# bicyclelab-manager-keyde-v4_0.net
KiCad netlist of a schematic drawn in EAGLE
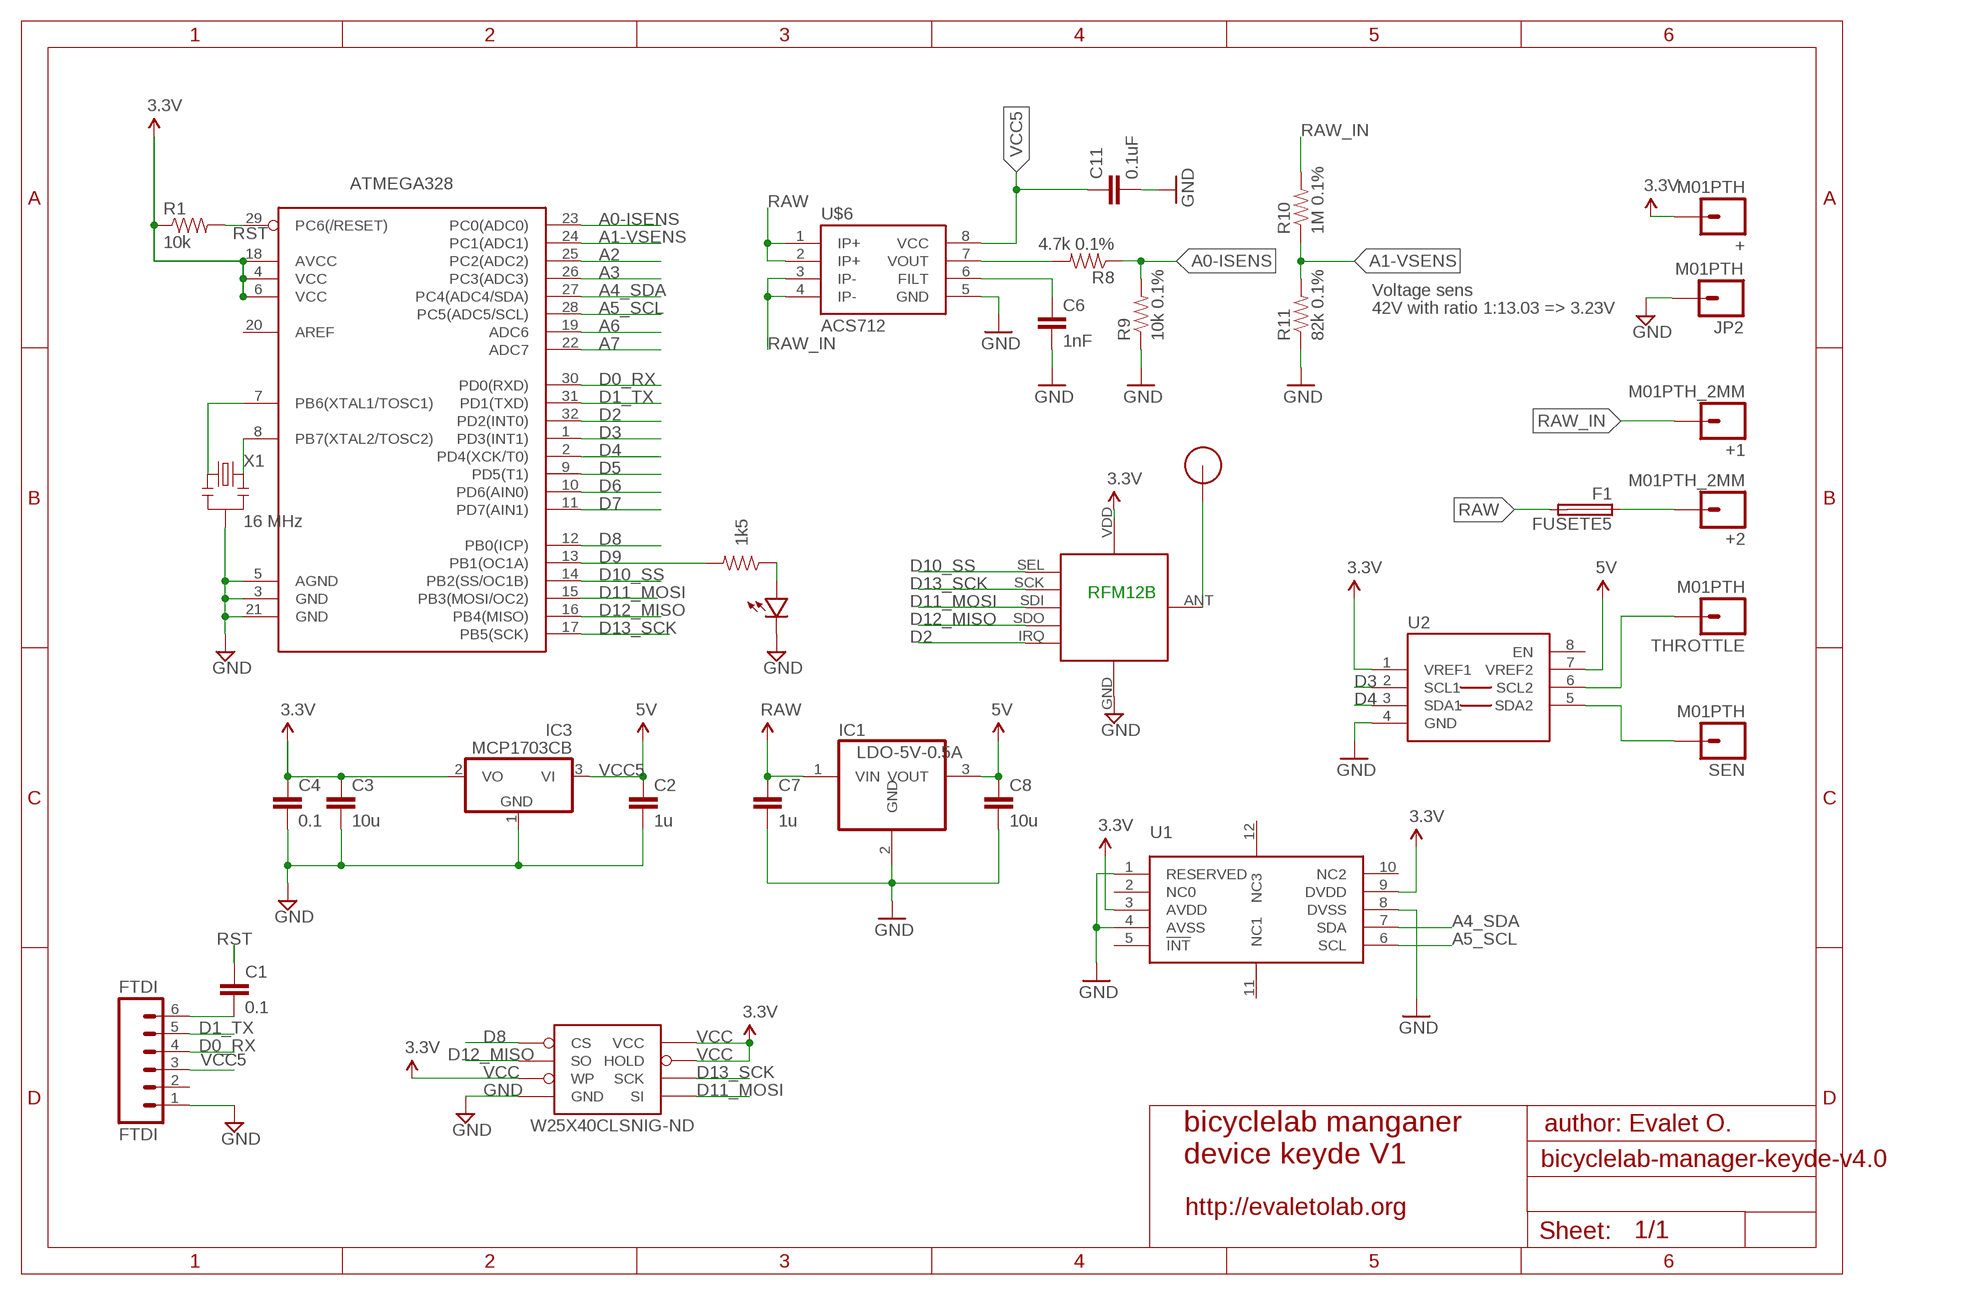
[diagram p0: schematic, sheet 1]

(export (version "E")
  (design (tool "Eeschema 10.0.6"))
  (components
    (comp (ref "+")
      (value "M01PTH")
      (footprint "eagle-import:1X01")
      (libsource (lib "eagle-import") (part "M01PTH"))
    )
    (comp (ref "+1")
      (value "M01PTH_2MM")
      (footprint "eagle-import:1X01_2MM")
      (libsource (lib "eagle-import") (part "M01PTH_2MM"))
    )
    (comp (ref "+2")
      (value "M01PTH_2MM")
      (footprint "eagle-import:1X01_2MM")
      (libsource (lib "eagle-import") (part "M01PTH_2MM"))
    )
    (comp (ref "ATMEGA328")
      (value "ATMega-328")
      (footprint "eagle-import:TQFP32-08")
      (libsource (lib "eagle-import") (part "ATMEGA168/328TQFP32"))
    )
    (comp (ref "C1")
      (value "0.1")
      (footprint "eagle-import:0603-CAP")
      (libsource (lib "eagle-import") (part "CAP0603-CAP"))
    )
    (comp (ref "C2")
      (value "1u")
      (footprint "eagle-import:0603-CAP")
      (libsource (lib "eagle-import") (part "CAP0603-CAP"))
    )
    (comp (ref "C3")
      (value "10u")
      (footprint "eagle-import:0805-CAP")
      (libsource (lib "eagle-import") (part "CAP0805-CAP"))
    )
    (comp (ref "C4")
      (value "0.1")
      (footprint "eagle-import:0603-CAP")
      (libsource (lib "eagle-import") (part "CAP0603-CAP"))
    )
    (comp (ref "C6")
      (value "1nF")
      (footprint "eagle-import:0805")
      (libsource (lib "eagle-import") (part "SparkFun_CAP0805"))
    )
    (comp (ref "C7")
      (value "1u")
      (footprint "eagle-import:0603-CAP")
      (libsource (lib "eagle-import") (part "CAP0603-CAP"))
    )
    (comp (ref "C8")
      (value "10u")
      (footprint "eagle-import:0805-CAP")
      (libsource (lib "eagle-import") (part "CAP0805-CAP"))
    )
    (comp (ref "C11")
      (value "0.1uF")
      (footprint "eagle-import:0805")
      (libsource (lib "eagle-import") (part "SparkFun_CAP0805"))
    )
    (comp (ref "F1")
      (value "FUSETE5")
      (footprint "eagle-import:TE5")
      (libsource (lib "eagle-import") (part "FUSETE5"))
    )
    (comp (ref "FTDI")
      (value "FTDI")
      (footprint "eagle-import:1X06")
      (libsource (lib "eagle-import") (part "M06SIP"))
    )
    (comp (ref "IC1")
      (value "LDO-5V-0.5A")
      (footprint "eagle-import:SOT223")
      (libsource (lib "eagle-import") (part "LDO-5V-0.5A"))
    )
    (comp (ref "IC3")
      (value "MCP1703CB")
      (footprint "eagle-import:SOT23")
      (libsource (lib "eagle-import") (part "MCP1703CB"))
    )
    (comp (ref "JP2")
      (value "M01PTH")
      (footprint "eagle-import:1X01")
      (libsource (lib "eagle-import") (part "M01PTH"))
    )
    (comp (ref "R1")
      (value "10k")
      (footprint "eagle-import:0603-RES")
      (libsource (lib "eagle-import") (part "RESISTOR0603-RES"))
    )
    (comp (ref "R2")
      (value "1k5")
      (footprint "eagle-import:0603-RES")
      (libsource (lib "eagle-import") (part "RESISTOR0603-RES"))
    )
    (comp (ref "R8")
      (value "4.7k 0.1%")
      (footprint "eagle-import:0805")
      (libsource (lib "eagle-import") (part "RESISTOR"))
    )
    (comp (ref "R9")
      (value "10k 0.1%")
      (footprint "eagle-import:0805")
      (libsource (lib "eagle-import") (part "RESISTOR"))
    )
    (comp (ref "R10")
      (value "1M 0.1%")
      (footprint "eagle-import:0805")
      (libsource (lib "eagle-import") (part "RESISTOR"))
    )
    (comp (ref "R11")
      (value "82k 0.1%")
      (footprint "eagle-import:0805")
      (libsource (lib "eagle-import") (part "RESISTOR"))
    )
    (comp (ref "RFM12B")
      (value "RFM12B_MINPADS")
      (footprint "eagle-import:RFM12B-MINPADS")
      (libsource (lib "eagle-import") (part "RFM12B_MINPADS"))
    )
    (comp (ref "SEN")
      (value "M01PTH")
      (footprint "eagle-import:1X01")
      (libsource (lib "eagle-import") (part "M01PTH"))
    )
    (comp (ref "THROTTLE")
      (value "M01PTH")
      (footprint "eagle-import:1X01")
      (libsource (lib "eagle-import") (part "M01PTH"))
    )
    (comp (ref "U$1")
      (value "RFM12B_ANTENNA")
      (footprint "eagle-import:RFM12B-ANTENNA")
      (libsource (lib "eagle-import") (part "RFM12B_ANTENNA"))
    )
    (comp (ref "U$2")
      (value "LED0603")
      (footprint "eagle-import:0603-LED")
      (libsource (lib "eagle-import") (part "LED0603"))
    )
    (comp (ref "U$6")
      (value "ACS712")
      (footprint "eagle-import:SO08")
      (libsource (lib "eagle-import") (part "ACS712"))
    )
    (comp (ref "U1")
      (value "MMA7660FC-DFN10")
      (footprint "eagle-import:DFN10")
      (libsource (lib "eagle-import") (part "MMA7660FC-DFN10"))
    )
    (comp (ref "U2")
      (value "PCA9306")
      (footprint "eagle-import:PSOP-8")
      (libsource (lib "eagle-import") (part "PCA9306"))
    )
    (comp (ref "W25X40CLSNIG-ND")
      (value "AT25F512BWIDE_5.3MM")
      (footprint "eagle-import:SO08WIDE")
      (libsource (lib "eagle-import") (part "AT25F512BWIDE_5.3MM"))
    )
    (comp (ref "X1")
      (value "16 MHz")
      (footprint "eagle-import:RESONATOR-SMD")
      (libsource (lib "eagle-import") (part "RESONATORSMD"))
    )
  )
  (nets
    (net (code "1") (name "/A2") (class "Default")
      (node (ref "ATMEGA328") (pin "25") (pinfunction "PC2(ADC2)_25") (pintype "bidirectional"))
    )
    (net (code "2") (name "/A3") (class "Default")
      (node (ref "ATMEGA328") (pin "26") (pinfunction "PC3(ADC3)_26") (pintype "bidirectional"))
    )
    (net (code "3") (name "/A4_SDA") (class "Default")
      (node (ref "ATMEGA328") (pin "27") (pinfunction "PC4(ADC4/SDA)_27") (pintype "bidirectional"))
      (node (ref "U1") (pin "7") (pinfunction "SDA_7") (pintype "bidirectional"))
    )
    (net (code "4") (name "/A5_SCL") (class "Default")
      (node (ref "ATMEGA328") (pin "28") (pinfunction "PC5(ADC5/SCL)_28") (pintype "bidirectional"))
      (node (ref "U1") (pin "6") (pinfunction "SCL_6") (pintype "bidirectional"))
    )
    (net (code "5") (name "/A6") (class "Default")
      (node (ref "ATMEGA328") (pin "19") (pinfunction "ADC6_19") (pintype "bidirectional"))
    )
    (net (code "6") (name "/A7") (class "Default")
      (node (ref "ATMEGA328") (pin "22") (pinfunction "ADC7_22") (pintype "bidirectional"))
    )
    (net (code "7") (name "/D0_RX") (class "Default")
      (node (ref "ATMEGA328") (pin "30") (pinfunction "PD0(RXD)_30") (pintype "bidirectional"))
      (node (ref "FTDI") (pin "4") (pinfunction "4_4") (pintype "passive"))
    )
    (net (code "8") (name "/D1_TX") (class "Default")
      (node (ref "ATMEGA328") (pin "31") (pinfunction "PD1(TXD)_31") (pintype "bidirectional"))
      (node (ref "FTDI") (pin "5") (pinfunction "5_5") (pintype "passive"))
    )
    (net (code "9") (name "/D2") (class "Default")
      (node (ref "ATMEGA328") (pin "32") (pinfunction "PD2(INT0)_32") (pintype "bidirectional"))
      (node (ref "RFM12B") (pin "IRQ") (pinfunction "IRQ_IRQ") (pintype "bidirectional"))
    )
    (net (code "10") (name "/D3") (class "Default")
      (node (ref "ATMEGA328") (pin "1") (pinfunction "PD3(INT1)_1") (pintype "bidirectional"))
      (node (ref "U2") (pin "2") (pinfunction "SCL1_2") (pintype "bidirectional"))
    )
    (net (code "11") (name "/D4") (class "Default")
      (node (ref "ATMEGA328") (pin "2") (pinfunction "PD4(XCK/T0)_2") (pintype "bidirectional"))
      (node (ref "U2") (pin "3") (pinfunction "SDA1_3") (pintype "bidirectional"))
    )
    (net (code "12") (name "/D5") (class "Default")
      (node (ref "ATMEGA328") (pin "9") (pinfunction "PD5(T1)_9") (pintype "bidirectional"))
    )
    (net (code "13") (name "/D6") (class "Default")
      (node (ref "ATMEGA328") (pin "10") (pinfunction "PD6(AIN0)_10") (pintype "bidirectional"))
    )
    (net (code "14") (name "/D7") (class "Default")
      (node (ref "ATMEGA328") (pin "11") (pinfunction "PD7(AIN1)_11") (pintype "bidirectional"))
    )
    (net (code "15") (name "/D8") (class "Default")
      (node (ref "ATMEGA328") (pin "12") (pinfunction "PB0(ICP)_12") (pintype "bidirectional"))
      (node (ref "W25X40CLSNIG-ND") (pin "1") (pinfunction "CS_1") (pintype "bidirectional"))
    )
    (net (code "16") (name "/D9") (class "Default")
      (node (ref "ATMEGA328") (pin "13") (pinfunction "PB1(OC1A)_13") (pintype "bidirectional"))
      (node (ref "R2") (pin "2") (pinfunction "2_2") (pintype "passive"))
    )
    (net (code "17") (name "/D10_SS") (class "Default")
      (node (ref "ATMEGA328") (pin "14") (pinfunction "PB2(SS/OC1B)_14") (pintype "bidirectional"))
      (node (ref "RFM12B") (pin "SEL") (pinfunction "SEL_SEL") (pintype "bidirectional"))
    )
    (net (code "18") (name "/D11_MOSI") (class "Default")
      (node (ref "ATMEGA328") (pin "15") (pinfunction "PB3(MOSI/OC2)_15") (pintype "bidirectional"))
      (node (ref "RFM12B") (pin "SDI") (pinfunction "SDI/MOSI_SDI") (pintype "bidirectional"))
      (node (ref "W25X40CLSNIG-ND") (pin "5") (pinfunction "SI_5") (pintype "bidirectional"))
    )
    (net (code "19") (name "/D12_MISO") (class "Default")
      (node (ref "ATMEGA328") (pin "16") (pinfunction "PB4(MISO)_16") (pintype "bidirectional"))
      (node (ref "RFM12B") (pin "SDO") (pinfunction "SDO/MISO_SDO") (pintype "bidirectional"))
      (node (ref "W25X40CLSNIG-ND") (pin "2") (pinfunction "SO_2") (pintype "bidirectional"))
    )
    (net (code "20") (name "/D13_SCK") (class "Default")
      (node (ref "ATMEGA328") (pin "17") (pinfunction "PB5(SCK)_17") (pintype "bidirectional"))
      (node (ref "RFM12B") (pin "SCK") (pinfunction "SCK_SCK") (pintype "bidirectional"))
      (node (ref "W25X40CLSNIG-ND") (pin "6") (pinfunction "SCK_6") (pintype "bidirectional"))
    )
    (net (code "21") (name "/RST") (class "Default")
      (node (ref "ATMEGA328") (pin "29") (pinfunction "PC6(/RESET)_29") (pintype "bidirectional"))
      (node (ref "C1") (pin "1") (pinfunction "1_1") (pintype "passive"))
      (node (ref "R1") (pin "2") (pinfunction "2_2") (pintype "passive"))
    )
    (net (code "22") (name "3.3V") (class "Default")
      (node (ref "+") (pin "1") (pinfunction "1_1") (pintype "passive"))
      (node (ref "ATMEGA328") (pin "18") (pinfunction "AVCC_18") (pintype "bidirectional"))
      (node (ref "ATMEGA328") (pin "4") (pinfunction "VCC_4") (pintype "bidirectional"))
      (node (ref "ATMEGA328") (pin "6") (pinfunction "VCC_6") (pintype "bidirectional"))
      (node (ref "C3") (pin "1") (pinfunction "1_1") (pintype "passive"))
      (node (ref "C4") (pin "1") (pinfunction "1_1") (pintype "passive"))
      (node (ref "IC3") (pin "2") (pinfunction "VO_2") (pintype "passive"))
      (node (ref "R1") (pin "1") (pinfunction "1_1") (pintype "passive"))
      (node (ref "RFM12B") (pin "VDD") (pinfunction "VDD_VDD") (pintype "bidirectional"))
      (node (ref "U1") (pin "3") (pinfunction "AVDD_3") (pintype "bidirectional"))
      (node (ref "U1") (pin "9") (pinfunction "DVDD_9") (pintype "bidirectional"))
      (node (ref "U2") (pin "1") (pinfunction "VREF1_1") (pintype "bidirectional"))
      (node (ref "W25X40CLSNIG-ND") (pin "3") (pinfunction "WP_3") (pintype "bidirectional"))
      (node (ref "W25X40CLSNIG-ND") (pin "7") (pinfunction "HOLD_7") (pintype "bidirectional"))
      (node (ref "W25X40CLSNIG-ND") (pin "8") (pinfunction "VCC_8") (pintype "bidirectional"))
    )
    (net (code "23") (name "A0-ISENS") (class "Default")
      (node (ref "ATMEGA328") (pin "23") (pinfunction "PC0(ADC0)_23") (pintype "bidirectional"))
      (node (ref "R8") (pin "1") (pinfunction "1_1") (pintype "passive"))
      (node (ref "R9") (pin "2") (pinfunction "2_2") (pintype "passive"))
    )
    (net (code "24") (name "A1-VSENS") (class "Default")
      (node (ref "ATMEGA328") (pin "24") (pinfunction "PC1(ADC1)_24") (pintype "bidirectional"))
      (node (ref "R10") (pin "1") (pinfunction "1_1") (pintype "passive"))
      (node (ref "R11") (pin "2") (pinfunction "2_2") (pintype "passive"))
    )
    (net (code "25") (name "GND") (class "Default")
      (node (ref "ATMEGA328") (pin "21") (pinfunction "GND_21") (pintype "bidirectional"))
      (node (ref "ATMEGA328") (pin "3") (pinfunction "GND_3") (pintype "bidirectional"))
      (node (ref "ATMEGA328") (pin "5") (pinfunction "AGND_5") (pintype "bidirectional"))
      (node (ref "C11") (pin "2") (pinfunction "2_2") (pintype "passive"))
      (node (ref "C2") (pin "2") (pinfunction "2_2") (pintype "passive"))
      (node (ref "C3") (pin "2") (pinfunction "2_2") (pintype "passive"))
      (node (ref "C4") (pin "2") (pinfunction "2_2") (pintype "passive"))
      (node (ref "C6") (pin "2") (pinfunction "2_2") (pintype "passive"))
      (node (ref "C7") (pin "2") (pinfunction "2_2") (pintype "passive"))
      (node (ref "C8") (pin "2") (pinfunction "2_2") (pintype "passive"))
      (node (ref "FTDI") (pin "1") (pinfunction "1_1") (pintype "passive"))
      (node (ref "IC1") (pin "2") (pinfunction "GND_2") (pintype "power_in"))
      (node (ref "IC3") (pin "1") (pinfunction "GND_1") (pintype "passive"))
      (node (ref "JP2") (pin "1") (pinfunction "1_1") (pintype "passive"))
      (node (ref "R11") (pin "1") (pinfunction "1_1") (pintype "passive"))
      (node (ref "R9") (pin "1") (pinfunction "1_1") (pintype "passive"))
      (node (ref "RFM12B") (pin "GND") (pinfunction "GND_GND") (pintype "bidirectional"))
      (node (ref "U$2") (pin "MINUS") (pinfunction "MINUS_MINUS") (pintype "passive"))
      (node (ref "U$6") (pin "5") (pinfunction "GND_5") (pintype "bidirectional"))
      (node (ref "U1") (pin "1") (pinfunction "RESERVED_1") (pintype "bidirectional"))
      (node (ref "U1") (pin "4") (pinfunction "AVSS_4") (pintype "bidirectional"))
      (node (ref "U1") (pin "8") (pinfunction "DVSS_8") (pintype "bidirectional"))
      (node (ref "U2") (pin "4") (pinfunction "GND_4") (pintype "bidirectional"))
      (node (ref "W25X40CLSNIG-ND") (pin "4") (pinfunction "GND_4") (pintype "bidirectional"))
      (node (ref "X1") (pin "2") (pinfunction "2_2") (pintype "passive"))
    )
    (net (code "26") (name "Net-(+2-Pad1)") (class "Default")
      (node (ref "+2") (pin "1") (pinfunction "1_1") (pintype "passive"))
      (node (ref "F1") (pin "1") (pinfunction "1_1") (pintype "passive"))
    )
    (net (code "27") (name "Net-(ATMEGA328-PB6(XTAL1{slash}TOSC1))") (class "Default")
      (node (ref "ATMEGA328") (pin "7") (pinfunction "PB6(XTAL1/TOSC1)_7") (pintype "bidirectional"))
      (node (ref "X1") (pin "1") (pinfunction "1_1") (pintype "passive"))
    )
    (net (code "28") (name "Net-(ATMEGA328-PB7(XTAL2{slash}TOSC2))") (class "Default")
      (node (ref "ATMEGA328") (pin "8") (pinfunction "PB7(XTAL2/TOSC2)_8") (pintype "bidirectional"))
      (node (ref "X1") (pin "3") (pinfunction "3_3") (pintype "passive"))
    )
    (net (code "29") (name "Net-(C1-Pad2)") (class "Default")
      (node (ref "C1") (pin "2") (pinfunction "2_2") (pintype "passive"))
      (node (ref "FTDI") (pin "6") (pinfunction "6_6") (pintype "passive"))
    )
    (net (code "30") (name "Net-(R2-Pad1)") (class "Default")
      (node (ref "R2") (pin "1") (pinfunction "1_1") (pintype "passive"))
      (node (ref "U$2") (pin "PLUS") (pinfunction "PLUS_PLUS") (pintype "passive"))
    )
    (net (code "31") (name "Net-(U$1-1)") (class "Default")
      (node (ref "RFM12B") (pin "ANT") (pinfunction "ANT_ANT") (pintype "bidirectional"))
      (node (ref "U$1") (pin "P$1") (pinfunction "1_P$1") (pintype "bidirectional"))
    )
    (net (code "32") (name "Net-(U$6-FILT)") (class "Default")
      (node (ref "C6") (pin "1") (pinfunction "1_1") (pintype "passive"))
      (node (ref "U$6") (pin "6") (pinfunction "FILT_6") (pintype "bidirectional"))
    )
    (net (code "33") (name "Net-(U$6-VOUT)") (class "Default")
      (node (ref "R8") (pin "2") (pinfunction "2_2") (pintype "passive"))
      (node (ref "U$6") (pin "7") (pinfunction "VOUT_7") (pintype "bidirectional"))
    )
    (net (code "34") (name "Net-(U2-SCL2)") (class "Default")
      (node (ref "THROTTLE") (pin "1") (pinfunction "1_1") (pintype "passive"))
      (node (ref "U2") (pin "6") (pinfunction "SCL2_6") (pintype "bidirectional"))
    )
    (net (code "35") (name "Net-(U2-SDA2)") (class "Default")
      (node (ref "SEN") (pin "1") (pinfunction "1_1") (pintype "passive"))
      (node (ref "U2") (pin "5") (pinfunction "SDA2_5") (pintype "bidirectional"))
    )
    (net (code "36") (name "RAW") (class "Default")
      (node (ref "C7") (pin "1") (pinfunction "1_1") (pintype "passive"))
      (node (ref "F1") (pin "2") (pinfunction "2_2") (pintype "passive"))
      (node (ref "IC1") (pin "1") (pinfunction "VIN_1") (pintype "input"))
      (node (ref "U$6") (pin "1") (pinfunction "IP+_1") (pintype "bidirectional"))
      (node (ref "U$6") (pin "2") (pinfunction "IP+_2") (pintype "bidirectional"))
    )
    (net (code "37") (name "RAW_IN") (class "Default")
      (node (ref "+1") (pin "1") (pinfunction "1_1") (pintype "passive"))
      (node (ref "R10") (pin "2") (pinfunction "2_2") (pintype "passive"))
      (node (ref "U$6") (pin "3") (pinfunction "IP-_3") (pintype "bidirectional"))
      (node (ref "U$6") (pin "4") (pinfunction "IP-_4") (pintype "bidirectional"))
    )
    (net (code "38") (name "VCC5") (class "Default")
      (node (ref "C11") (pin "1") (pinfunction "1_1") (pintype "passive"))
      (node (ref "C2") (pin "1") (pinfunction "1_1") (pintype "passive"))
      (node (ref "C8") (pin "1") (pinfunction "1_1") (pintype "passive"))
      (node (ref "FTDI") (pin "3") (pinfunction "3_3") (pintype "passive"))
      (node (ref "IC1") (pin "3") (pinfunction "VOUT_3") (pintype "output"))
      (node (ref "IC3") (pin "3") (pinfunction "VI_3") (pintype "input"))
      (node (ref "U$6") (pin "8") (pinfunction "VCC_8") (pintype "bidirectional"))
      (node (ref "U2") (pin "7") (pinfunction "VREF2_7") (pintype "bidirectional"))
    )
    (net (code "39") (name "unconnected-(ATMEGA328-AREF-Pad20)") (class "Default")
      (node (ref "ATMEGA328") (pin "20") (pinfunction "AREF_20") (pintype "bidirectional"))
    )
    (net (code "40") (name "unconnected-(FTDI-Pad2)") (class "Default")
      (node (ref "FTDI") (pin "2") (pinfunction "2_2") (pintype "passive"))
    )
    (net (code "41") (name "unconnected-(U1-NC0-Pad2)") (class "Default")
      (node (ref "U1") (pin "2") (pinfunction "NC0_2") (pintype "bidirectional"))
    )
    (net (code "42") (name "unconnected-(U1-NC1-Pad11)") (class "Default")
      (node (ref "U1") (pin "11") (pinfunction "NC1_11") (pintype "bidirectional"))
    )
    (net (code "43") (name "unconnected-(U1-NC2-Pad10)") (class "Default")
      (node (ref "U1") (pin "10") (pinfunction "NC2_10") (pintype "bidirectional"))
    )
    (net (code "44") (name "unconnected-(U1-NC3-Pad12)") (class "Default")
      (node (ref "U1") (pin "12") (pinfunction "NC3_12") (pintype "bidirectional"))
    )
    (net (code "45") (name "unconnected-(U1-~{INT}-Pad5)") (class "Default")
      (node (ref "U1") (pin "5") (pinfunction "~{INT}_5") (pintype "bidirectional"))
    )
    (net (code "46") (name "unconnected-(U2-EN-Pad8)") (class "Default")
      (node (ref "U2") (pin "8") (pinfunction "EN_8") (pintype "bidirectional"))
    )
  )
)
